# schematic.net
KiCad netlist of a schematic drawn in EasyEDA
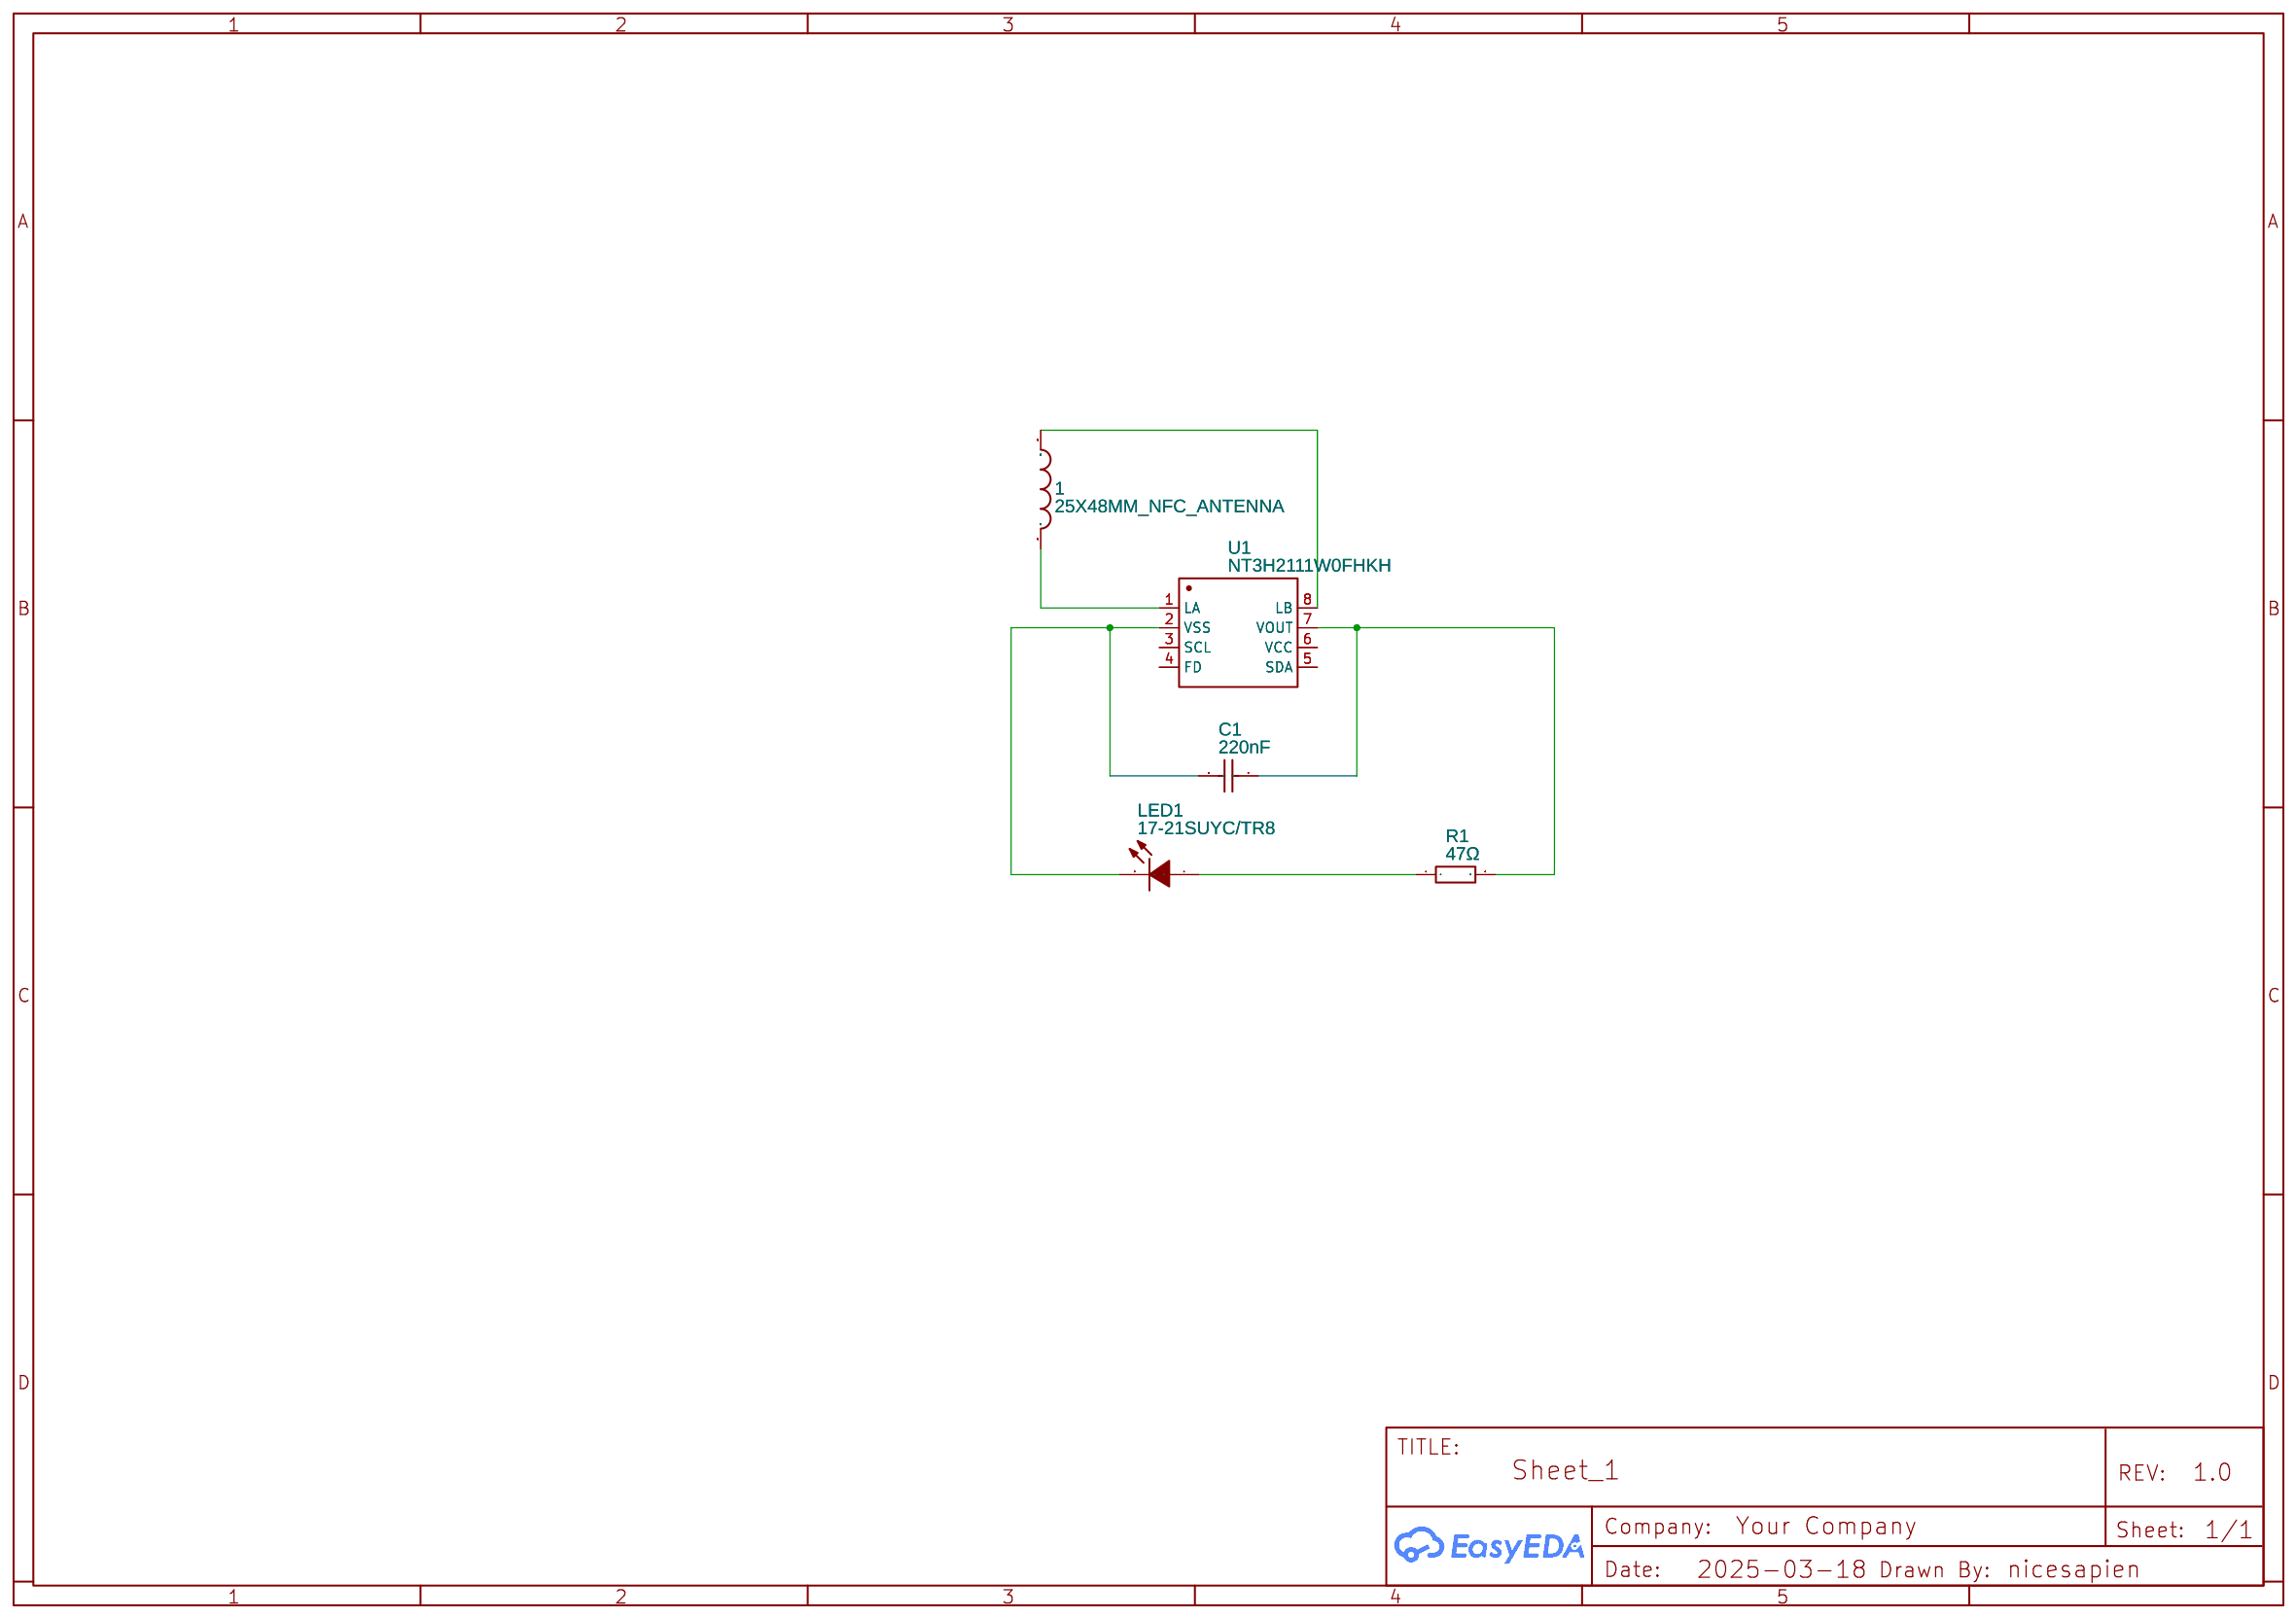
[diagram p0: schematic sheet]

(export (version "E")
  (design (tool "Eeschema 10.0.6"))
  (components
    (comp (ref "1") (value "25X48MM_NFC_ANTENNA") (libsource (lib "") (part "25X48MM_NFC_ANTENNA")))
    (comp (ref "C1")
      (value "220nF")
      (fields
        (field (name "Manufacturer Part") "CL10B224KA8NNNC")
        (field (name "Manufacturer") "SAMSUNG(三星)")
      )
      (libsource (lib "") (part "CL10B224KA8NNNC"))
    )
    (comp (ref "LED1")
      (value "17-21SUYC/TR8")
      (fields (field (name "Manufacturer Part") "KT-0805黄灯") (field (name "Manufacturer") "KENTO"))
      (libsource (lib "") (part "17-21SUYC/TR8"))
    )
    (comp (ref "R1")
      (value "47Ω")
      (fields
        (field (name "Manufacturer Part") "0603WAF470JT5E")
        (field (name "Manufacturer") "UNI-ROYAL(厚声)")
      )
      (libsource (lib "") (part "0603WAF470JT5E"))
    )
    (comp (ref "U1")
      (value "NT3H2111W0FHKH")
      (fields (field (name "Manufacturer") "NXP(恩智浦)"))
      (libsource (lib "") (part "NT3H2111W0FHKH"))
    )
  )
  (nets
    (net (code "1") (name "Net-(LED1-+)") (class "Default")
      (node (ref "LED1") (pin "1") (pinfunction "+_1") (pintype "unspecified"))
      (node (ref "R1") (pin "1") (pinfunction "1_1") (pintype "input"))
    )
    (net (code "2") (name "Net-(LED1--)") (class "Default")
      (node (ref "C1") (pin "1") (pinfunction "1_1") (pintype "input"))
      (node (ref "LED1") (pin "2") (pinfunction "-_2") (pintype "unspecified"))
      (node (ref "U1") (pin "2") (pinfunction "VSS_2") (pintype "unspecified"))
    )
    (net (code "3") (name "Net-(U1-LA)") (class "Default")
      (node (ref "1") (pin "P$2") (pinfunction "P$2_P$2") (pintype "bidirectional"))
      (node (ref "U1") (pin "1") (pinfunction "LA_1") (pintype "unspecified"))
    )
    (net (code "4") (name "Net-(U1-LB)") (class "Default")
      (node (ref "1") (pin "P$1") (pinfunction "P$1_P$1") (pintype "bidirectional"))
      (node (ref "U1") (pin "8") (pinfunction "LB_8") (pintype "unspecified"))
    )
    (net (code "5") (name "Net-(U1-VOUT)") (class "Default")
      (node (ref "C1") (pin "2") (pinfunction "2_2") (pintype "input"))
      (node (ref "R1") (pin "2") (pinfunction "2_2") (pintype "input"))
      (node (ref "U1") (pin "7") (pinfunction "VOUT_7") (pintype "unspecified"))
    )
    (net (code "6") (name "unconnected-(U1-FD-Pad4)") (class "Default")
      (node (ref "U1") (pin "4") (pinfunction "FD_4") (pintype "unspecified"))
    )
    (net (code "7") (name "unconnected-(U1-SCL-Pad3)") (class "Default")
      (node (ref "U1") (pin "3") (pinfunction "SCL_3") (pintype "unspecified"))
    )
    (net (code "8") (name "unconnected-(U1-SDA-Pad5)") (class "Default")
      (node (ref "U1") (pin "5") (pinfunction "SDA_5") (pintype "unspecified"))
    )
    (net (code "9") (name "unconnected-(U1-VCC-Pad6)") (class "Default")
      (node (ref "U1") (pin "6") (pinfunction "VCC_6") (pintype "unspecified"))
    )
  )
)
